# div71-eagle.net
KiCad netlist of a schematic drawn in EAGLE
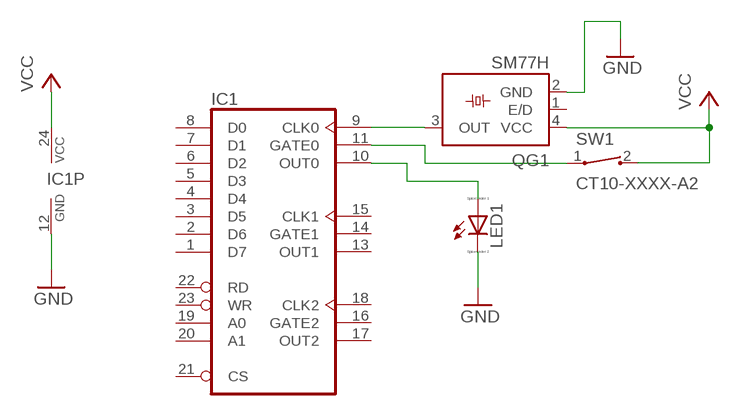
[diagram p0: schematic, sheet 1]

(export (version "E")
  (design (tool "Eeschema 10.0.6"))
  (components
    (comp (ref "IC1")
      (value "8253")
      (footprint "eagle-import:DIL24-6")
      (libsource (lib "eagle-import") (part "8253"))
    )
    (comp (ref "LED1")
      (value "LED_E")
      (footprint "eagle-import:LED_1206")
      (libsource (lib "eagle-import") (part "LED_E"))
    )
    (comp (ref "QG1")
      (value "SM77H")
      (footprint "eagle-import:SM77H")
      (libsource (lib "eagle-import") (part "SM77H"))
    )
    (comp (ref "SW1")
      (value "CT10-XXXX-A2")
      (footprint "eagle-import:CT10-XXXX-A2")
      (libsource (lib "eagle-import") (part "CT10-XXXX-A2"))
    )
  )
  (nets
    (net (code "1") (name "GND") (class "Default")
      (node (ref "IC1") (pin "12") (pinfunction "GND_12") (pintype "power_in"))
      (node (ref "LED1") (pin "C") (pinfunction "C_C") (pintype "passive"))
      (node (ref "QG1") (pin "2") (pinfunction "GND_2") (pintype "power_in"))
    )
    (net (code "2") (name "Net-(IC1A-CLK0)") (class "Default")
      (node (ref "IC1") (pin "9") (pinfunction "CLK0_9") (pintype "input"))
      (node (ref "QG1") (pin "3") (pinfunction "OUT_3") (pintype "output"))
    )
    (net (code "3") (name "Net-(IC1A-GATE0)") (class "Default")
      (node (ref "IC1") (pin "11") (pinfunction "GATE0_11") (pintype "input"))
      (node (ref "SW1") (pin "1") (pinfunction "1_1") (pintype "passive"))
    )
    (net (code "4") (name "Net-(IC1A-OUT0)") (class "Default")
      (node (ref "IC1") (pin "10") (pinfunction "OUT0_10") (pintype "output"))
      (node (ref "LED1") (pin "A") (pinfunction "A_A") (pintype "passive"))
    )
    (net (code "5") (name "VCC") (class "Default")
      (node (ref "IC1") (pin "24") (pinfunction "VCC_24") (pintype "power_in"))
      (node (ref "QG1") (pin "4") (pinfunction "VCC_4") (pintype "power_in"))
      (node (ref "SW1") (pin "2") (pinfunction "2_2") (pintype "passive"))
    )
    (net (code "6") (name "unconnected-(IC1A-A0-Pad19)") (class "Default")
      (node (ref "IC1") (pin "19") (pinfunction "A0_19") (pintype "input"))
    )
    (net (code "7") (name "unconnected-(IC1A-A1-Pad20)") (class "Default")
      (node (ref "IC1") (pin "20") (pinfunction "A1_20") (pintype "input"))
    )
    (net (code "8") (name "unconnected-(IC1A-CLK1-Pad15)") (class "Default")
      (node (ref "IC1") (pin "15") (pinfunction "CLK1_15") (pintype "input"))
    )
    (net (code "9") (name "unconnected-(IC1A-CLK2-Pad18)") (class "Default")
      (node (ref "IC1") (pin "18") (pinfunction "CLK2_18") (pintype "input"))
    )
    (net (code "10") (name "unconnected-(IC1A-CS-Pad21)") (class "Default")
      (node (ref "IC1") (pin "21") (pinfunction "CS_21") (pintype "input"))
    )
    (net (code "11") (name "unconnected-(IC1A-D0-Pad8)") (class "Default")
      (node (ref "IC1") (pin "8") (pinfunction "D0_8") (pintype "bidirectional"))
    )
    (net (code "12") (name "unconnected-(IC1A-D1-Pad7)") (class "Default")
      (node (ref "IC1") (pin "7") (pinfunction "D1_7") (pintype "bidirectional"))
    )
    (net (code "13") (name "unconnected-(IC1A-D2-Pad6)") (class "Default")
      (node (ref "IC1") (pin "6") (pinfunction "D2_6") (pintype "bidirectional"))
    )
    (net (code "14") (name "unconnected-(IC1A-D3-Pad5)") (class "Default")
      (node (ref "IC1") (pin "5") (pinfunction "D3_5") (pintype "bidirectional"))
    )
    (net (code "15") (name "unconnected-(IC1A-D4-Pad4)") (class "Default")
      (node (ref "IC1") (pin "4") (pinfunction "D4_4") (pintype "bidirectional"))
    )
    (net (code "16") (name "unconnected-(IC1A-D5-Pad3)") (class "Default")
      (node (ref "IC1") (pin "3") (pinfunction "D5_3") (pintype "bidirectional"))
    )
    (net (code "17") (name "unconnected-(IC1A-D6-Pad2)") (class "Default")
      (node (ref "IC1") (pin "2") (pinfunction "D6_2") (pintype "bidirectional"))
    )
    (net (code "18") (name "unconnected-(IC1A-D7-Pad1)") (class "Default")
      (node (ref "IC1") (pin "1") (pinfunction "D7_1") (pintype "bidirectional"))
    )
    (net (code "19") (name "unconnected-(IC1A-GATE1-Pad14)") (class "Default")
      (node (ref "IC1") (pin "14") (pinfunction "GATE1_14") (pintype "input"))
    )
    (net (code "20") (name "unconnected-(IC1A-GATE2-Pad16)") (class "Default")
      (node (ref "IC1") (pin "16") (pinfunction "GATE2_16") (pintype "input"))
    )
    (net (code "21") (name "unconnected-(IC1A-OUT1-Pad13)") (class "Default")
      (node (ref "IC1") (pin "13") (pinfunction "OUT1_13") (pintype "output"))
    )
    (net (code "22") (name "unconnected-(IC1A-OUT2-Pad17)") (class "Default")
      (node (ref "IC1") (pin "17") (pinfunction "OUT2_17") (pintype "output"))
    )
    (net (code "23") (name "unconnected-(IC1A-RD-Pad22)") (class "Default")
      (node (ref "IC1") (pin "22") (pinfunction "RD_22") (pintype "input"))
    )
    (net (code "24") (name "unconnected-(IC1A-WR-Pad23)") (class "Default")
      (node (ref "IC1") (pin "23") (pinfunction "WR_23") (pintype "input"))
    )
    (net (code "25") (name "unconnected-(QG1-E{slash}D-Pad1)") (class "Default")
      (node (ref "QG1") (pin "1") (pinfunction "E/D_1") (pintype "input"))
    )
  )
)
